# design1.net
KiCad netlist of a schematic drawn in EAGLE
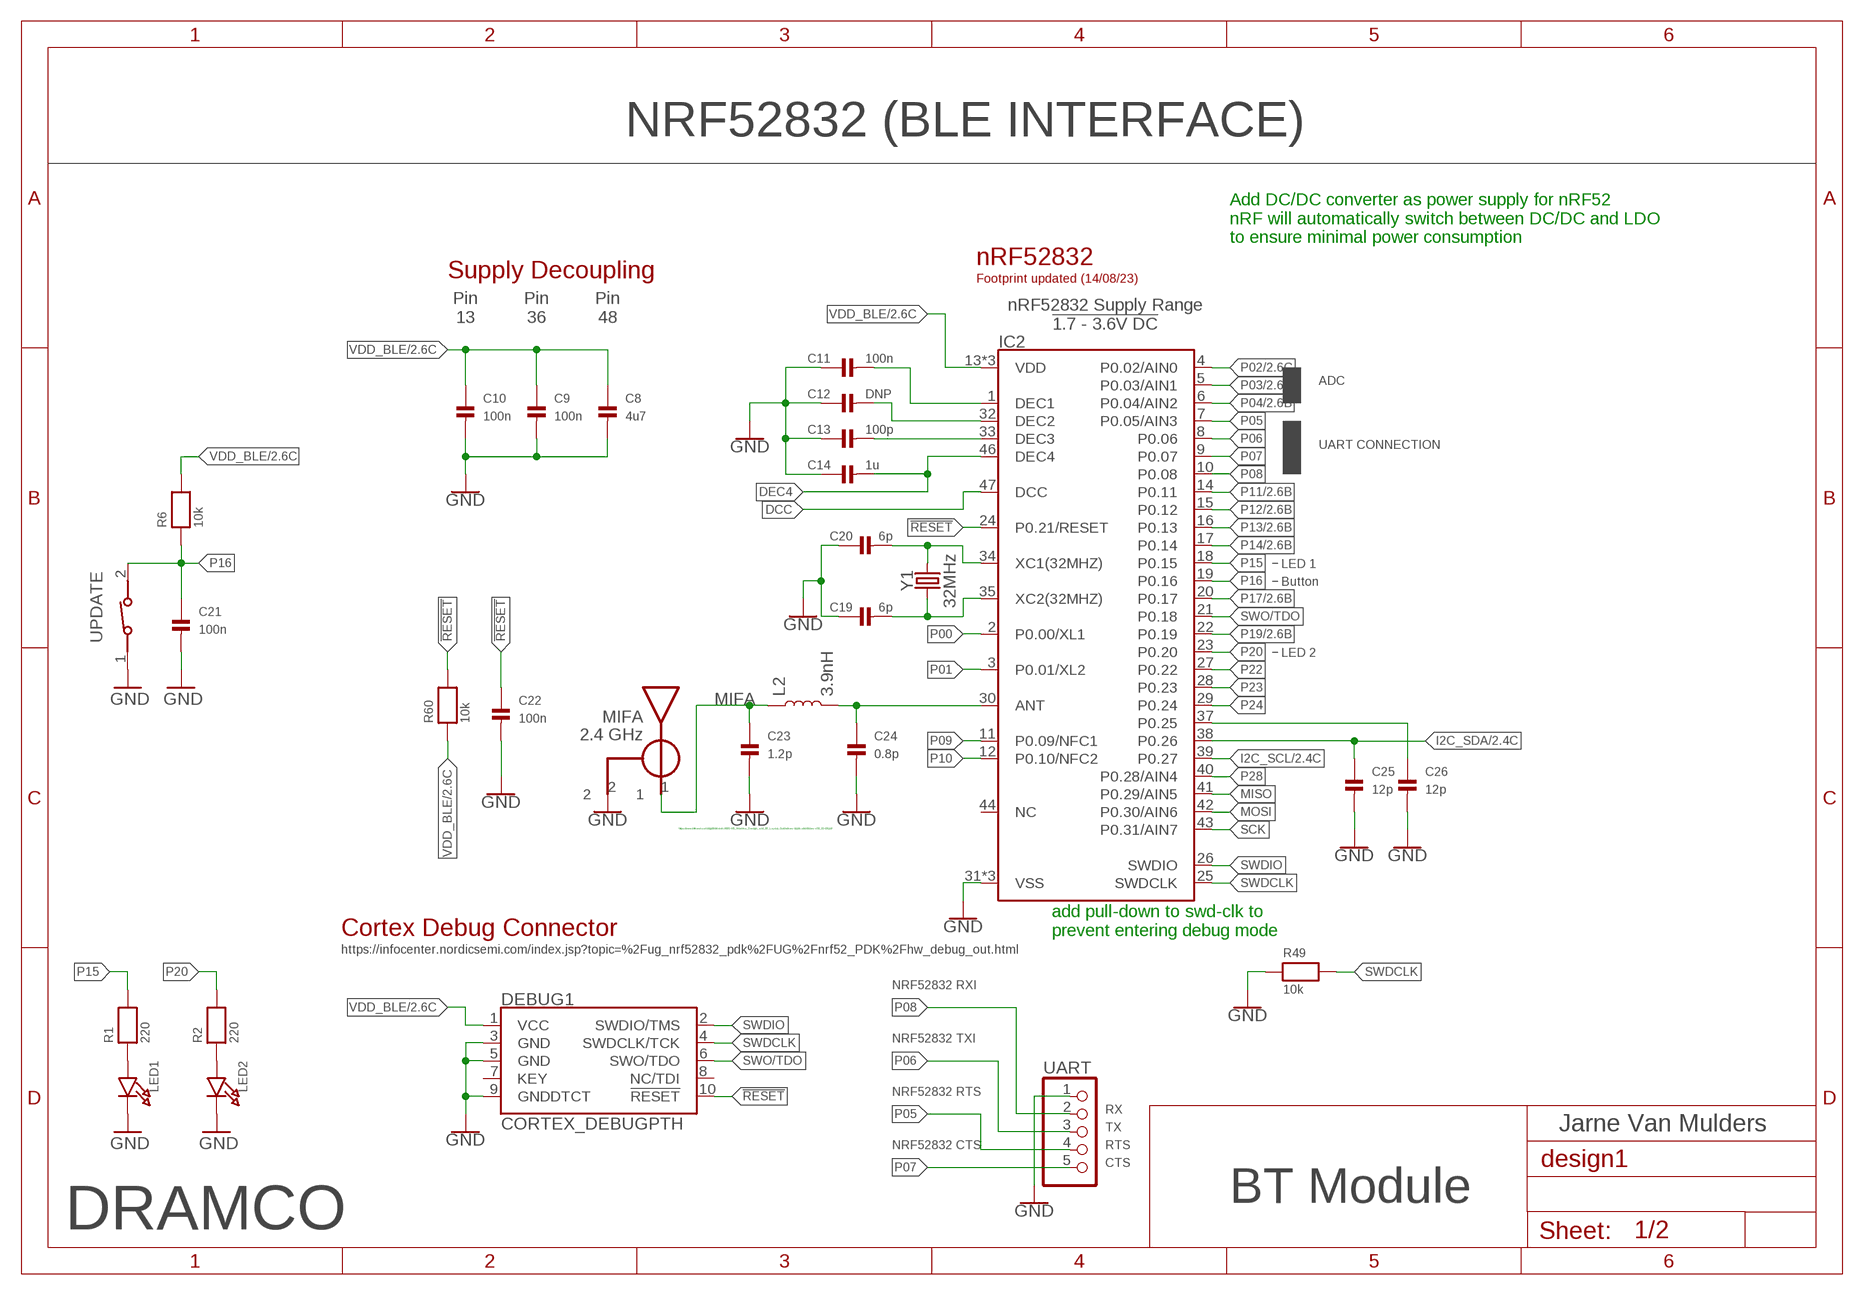
[diagram p0: schematic, sheet 1]
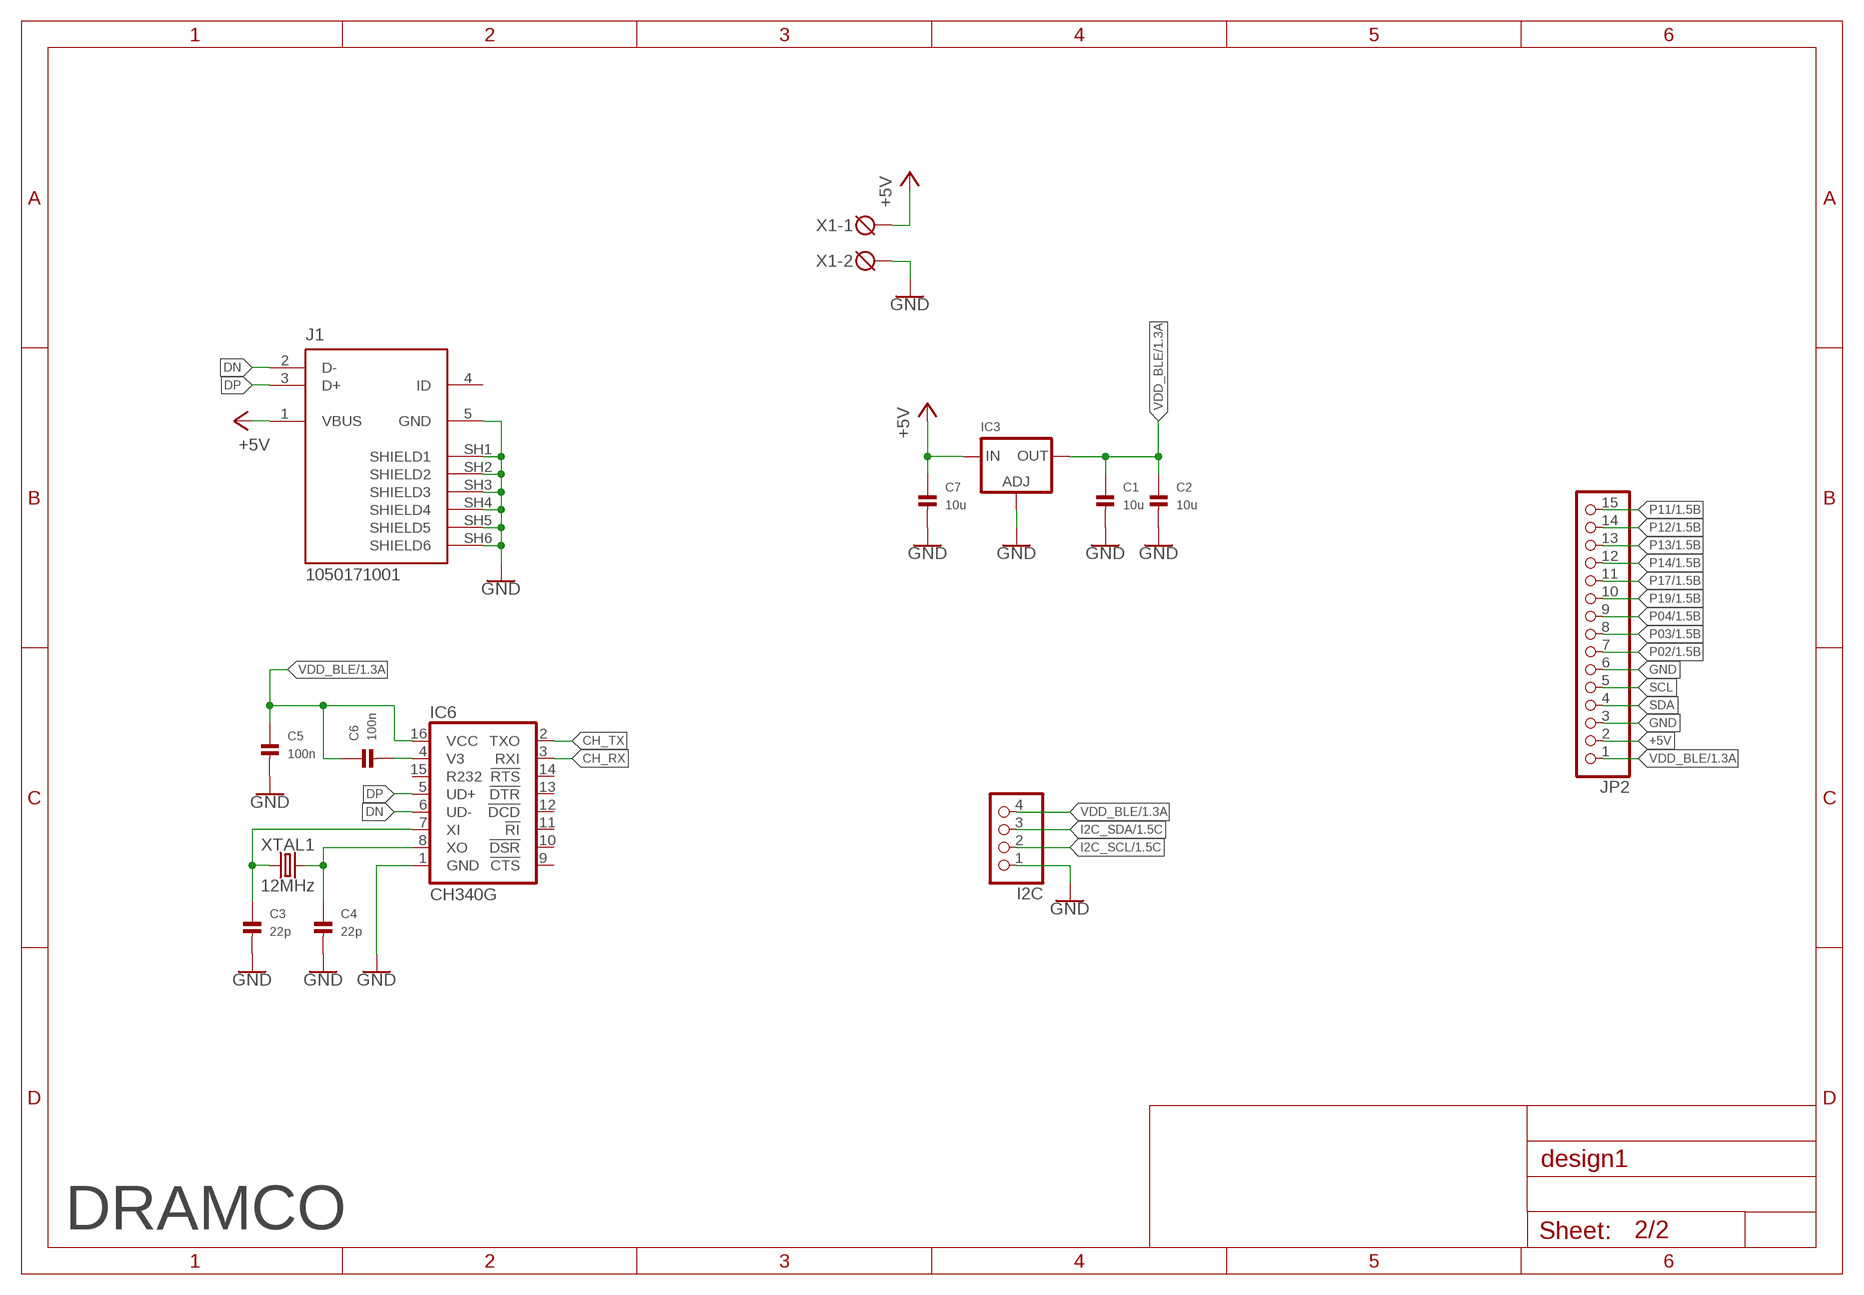
[diagram p1: schematic, sheet 2]

(export (version "E")
  (design (tool "Eeschema 10.0.6"))
  (components
    (comp (ref "C1")
      (value "10u")
      (footprint "eagle-import:0805")
      (libsource (lib "eagle-import") (part "CAP_CERAMIC0805"))
    )
    (comp (ref "C2")
      (value "10u")
      (footprint "eagle-import:0805")
      (libsource (lib "eagle-import") (part "CAP_CERAMIC0805"))
    )
    (comp (ref "C3")
      (value "22p")
      (footprint "eagle-import:0402")
      (libsource (lib "eagle-import") (part "CAP_CERAMIC0402"))
    )
    (comp (ref "C4")
      (value "22p")
      (footprint "eagle-import:0402")
      (libsource (lib "eagle-import") (part "CAP_CERAMIC0402"))
    )
    (comp (ref "C5")
      (value "100n")
      (footprint "eagle-import:0402")
      (libsource (lib "eagle-import") (part "CAP_CERAMIC0402"))
    )
    (comp (ref "C6")
      (value "100n")
      (footprint "eagle-import:0402")
      (libsource (lib "eagle-import") (part "CAP_CERAMIC0402"))
    )
    (comp (ref "C7")
      (value "10u")
      (footprint "eagle-import:0805")
      (libsource (lib "eagle-import") (part "CAP_CERAMIC0805"))
    )
    (comp (ref "I2C")
      (value "HEADER-1X4ROUND")
      (footprint "eagle-import:1X04_ROUND")
      (libsource (lib "eagle-import") (part "HEADER-1X4ROUND"))
    )
    (comp (ref "IC3")
      (value "LM1117SOT223-REFLOW")
      (footprint "eagle-import:SOT223-R")
      (libsource (lib "eagle-import") (part "LM1117SOT223-REFLOW"))
    )
    (comp (ref "IC6")
      (value "CH340G")
      (footprint "eagle-import:SO016")
      (libsource (lib "eagle-import") (part "CH340GSMD"))
    )
    (comp (ref "J1")
      (value "1050171001")
      (footprint "eagle-import:MOLEX_1050171001")
      (fields (field (name "MF") "Molex"))
      (libsource (lib "eagle-import") (part "1050171001"))
    )
    (comp (ref "JP2")
      (value "HEADER-1X15")
      (footprint "eagle-import:1X15_ROUND_70")
      (libsource (lib "eagle-import") (part "HEADER-1X15"))
    )
    (comp (ref "X1")
      (value "DG3XX-02-3.5")
      (footprint "eagle-import:DG350-3.5-02P")
      (libsource (lib "eagle-import") (part "DG3XX-02-3.5"))
    )
    (comp (ref "XTAL1")
      (value "12MHz")
      (footprint "eagle-import:CRYSTAL-SMD-3.2X2.5MM")
      (libsource (lib "eagle-import") (part "CRYSTALSMD-3.2X2.5"))
    )
    (comp (ref "C8")
      (value "4u7")
      (footprint "eagle-import:0603")
      (libsource (lib "eagle-import") (part "CAP_CERAMIC0603"))
    )
    (comp (ref "C9")
      (value "100n")
      (footprint "eagle-import:0402")
      (libsource (lib "eagle-import") (part "CAP_CERAMIC0402"))
    )
    (comp (ref "C10")
      (value "100n")
      (footprint "eagle-import:0402")
      (libsource (lib "eagle-import") (part "CAP_CERAMIC0402"))
    )
    (comp (ref "C11")
      (value "100n")
      (footprint "eagle-import:0402")
      (libsource (lib "eagle-import") (part "CAP_CERAMIC0402"))
    )
    (comp (ref "C12")
      (value "DNP")
      (footprint "eagle-import:0402")
      (libsource (lib "eagle-import") (part "CAP_CERAMIC0402"))
    )
    (comp (ref "C13")
      (value "100p")
      (footprint "eagle-import:0402")
      (libsource (lib "eagle-import") (part "CAP_CERAMIC0402"))
    )
    (comp (ref "C14")
      (value "1u")
      (footprint "eagle-import:0402")
      (libsource (lib "eagle-import") (part "CAP_CERAMIC0402"))
    )
    (comp (ref "C19")
      (value "6p")
      (footprint "eagle-import:0402")
      (libsource (lib "eagle-import") (part "CAP_CERAMIC0402"))
    )
    (comp (ref "C20")
      (value "6p")
      (footprint "eagle-import:0402")
      (libsource (lib "eagle-import") (part "CAP_CERAMIC0402"))
    )
    (comp (ref "C21")
      (value "100n")
      (footprint "eagle-import:0402")
      (libsource (lib "eagle-import") (part "CAP_CERAMIC0402"))
    )
    (comp (ref "C22")
      (value "100n")
      (footprint "eagle-import:0402")
      (libsource (lib "eagle-import") (part "CAP_CERAMIC0402"))
    )
    (comp (ref "C23")
      (value "1.2p")
      (footprint "eagle-import:0402")
      (libsource (lib "eagle-import") (part "CAP_CERAMIC0402"))
    )
    (comp (ref "C24")
      (value "0.8p")
      (footprint "eagle-import:0402")
      (libsource (lib "eagle-import") (part "CAP_CERAMIC0402"))
    )
    (comp (ref "C25")
      (value "12p")
      (footprint "eagle-import:0402")
      (libsource (lib "eagle-import") (part "CAP_CERAMIC0402"))
    )
    (comp (ref "C26")
      (value "12p")
      (footprint "eagle-import:0402")
      (libsource (lib "eagle-import") (part "CAP_CERAMIC0402"))
    )
    (comp (ref "DEBUG1")
      (value "CORTEX_DEBUGPTH")
      (footprint "eagle-import:2X5-PTH-1.27MM")
      (libsource (lib "eagle-import") (part "CORTEX_DEBUGPTH"))
    )
    (comp (ref "IC2")
      (value "NRF52832-EXTENDED")
      (footprint "eagle-import:QFN48-6X6MM-EXTENDED")
      (libsource (lib "eagle-import") (part "NRF52832-EXTENDED"))
    )
    (comp (ref "L2")
      (value "3.9nH")
      (footprint "eagle-import:0402")
      (libsource (lib "eagle-import") (part "INDUCTOR-0402-3.9NH"))
    )
    (comp (ref "LED1")
      (value "LED0805")
      (footprint "eagle-import:CHIPLED_0805")
      (libsource (lib "eagle-import") (part "LED0805"))
    )
    (comp (ref "LED2")
      (value "LED0805")
      (footprint "eagle-import:CHIPLED_0805")
      (libsource (lib "eagle-import") (part "LED0805"))
    )
    (comp (ref "R1")
      (value "220")
      (footprint "eagle-import:0603")
      (libsource (lib "eagle-import") (part "RESISTOR0603"))
    )
    (comp (ref "R2")
      (value "220")
      (footprint "eagle-import:0603")
      (libsource (lib "eagle-import") (part "RESISTOR0603"))
    )
    (comp (ref "R6")
      (value "10k")
      (footprint "eagle-import:0402")
      (libsource (lib "eagle-import") (part "RESISTOR0402"))
    )
    (comp (ref "R49")
      (value "10k")
      (footprint "eagle-import:0402")
      (libsource (lib "eagle-import") (part "RESISTOR0402"))
    )
    (comp (ref "R60")
      (value "10k")
      (footprint "eagle-import:0402")
      (libsource (lib "eagle-import") (part "RESISTOR0402"))
    )
    (comp (ref "U$18")
      (value "BLE-ANT")
      (footprint "eagle-import:ANT-2G4")
      (libsource (lib "eagle-import") (part "BLE-ANT"))
    )
    (comp (ref "UART")
      (value "HEADER-1X5ROUND")
      (footprint "eagle-import:1X05_ROUND")
      (libsource (lib "eagle-import") (part "HEADER-1X5ROUND"))
    )
    (comp (ref "UPDATE")
      (value "434111043826")
      (footprint "eagle-import:434111043826")
      (libsource (lib "eagle-import") (part "434111043826"))
    )
    (comp (ref "Y1")
      (value "32MHz")
      (footprint "eagle-import:CRYSTAL-SMD-2.0X1.6MM")
      (libsource (lib "eagle-import") (part "CRYSTAL-32MHZ-SMD-2.0X1.6MM"))
    )
  )
  (nets
    (net (code "1") (name "+5V") (class "Default")
      (node (ref "C7") (pin "1") (pinfunction "P$1_1") (pintype "passive"))
      (node (ref "IC3") (pin "3") (pinfunction "IN_3") (pintype "input"))
      (node (ref "J1") (pin "1") (pinfunction "VBUS_1") (pintype "power_in"))
      (node (ref "JP2") (pin "2") (pinfunction "2_2") (pintype "passive"))
      (node (ref "X1") (pin "1") (pinfunction "KL_1") (pintype "passive"))
    )
    (net (code "2") (name "CH_RX") (class "Default")
      (node (ref "IC6") (pin "3") (pinfunction "RXI_3") (pintype "bidirectional"))
    )
    (net (code "3") (name "CH_TX") (class "Default")
      (node (ref "IC6") (pin "2") (pinfunction "TXO_2") (pintype "bidirectional"))
    )
    (net (code "4") (name "DCC") (class "Default")
      (node (ref "IC2") (pin "47") (pinfunction "DCC_47") (pintype "bidirectional"))
    )
    (net (code "5") (name "DEC4") (class "Default")
      (node (ref "C14") (pin "2") (pinfunction "P$2_2") (pintype "passive"))
      (node (ref "IC2") (pin "46") (pinfunction "DEC4_46") (pintype "bidirectional"))
    )
    (net (code "6") (name "DN") (class "Default")
      (node (ref "IC6") (pin "6") (pinfunction "UD-_6") (pintype "bidirectional"))
      (node (ref "J1") (pin "2") (pinfunction "D-_2") (pintype "bidirectional"))
    )
    (net (code "7") (name "DP") (class "Default")
      (node (ref "IC6") (pin "5") (pinfunction "UD+_5") (pintype "bidirectional"))
      (node (ref "J1") (pin "3") (pinfunction "D+_3") (pintype "bidirectional"))
    )
    (net (code "8") (name "GND") (class "Default")
      (node (ref "C1") (pin "2") (pinfunction "P$2_2") (pintype "passive"))
      (node (ref "C10") (pin "2") (pinfunction "P$2_2") (pintype "passive"))
      (node (ref "C11") (pin "1") (pinfunction "P$1_1") (pintype "passive"))
      (node (ref "C12") (pin "1") (pinfunction "P$1_1") (pintype "passive"))
      (node (ref "C13") (pin "1") (pinfunction "P$1_1") (pintype "passive"))
      (node (ref "C14") (pin "1") (pinfunction "P$1_1") (pintype "passive"))
      (node (ref "C19") (pin "1") (pinfunction "P$1_1") (pintype "passive"))
      (node (ref "C2") (pin "2") (pinfunction "P$2_2") (pintype "passive"))
      (node (ref "C20") (pin "1") (pinfunction "P$1_1") (pintype "passive"))
      (node (ref "C21") (pin "2") (pinfunction "P$2_2") (pintype "passive"))
      (node (ref "C22") (pin "2") (pinfunction "P$2_2") (pintype "passive"))
      (node (ref "C23") (pin "2") (pinfunction "P$2_2") (pintype "passive"))
      (node (ref "C24") (pin "2") (pinfunction "P$2_2") (pintype "passive"))
      (node (ref "C25") (pin "2") (pinfunction "P$2_2") (pintype "passive"))
      (node (ref "C26") (pin "2") (pinfunction "P$2_2") (pintype "passive"))
      (node (ref "C3") (pin "2") (pinfunction "P$2_2") (pintype "passive"))
      (node (ref "C4") (pin "2") (pinfunction "P$2_2") (pintype "passive"))
      (node (ref "C5") (pin "2") (pinfunction "P$2_2") (pintype "passive"))
      (node (ref "C7") (pin "2") (pinfunction "P$2_2") (pintype "passive"))
      (node (ref "C8") (pin "2") (pinfunction "P$2_2") (pintype "passive"))
      (node (ref "C9") (pin "2") (pinfunction "P$2_2") (pintype "passive"))
      (node (ref "DEBUG1") (pin "3") (pinfunction "GND_3") (pintype "bidirectional"))
      (node (ref "DEBUG1") (pin "5") (pinfunction "GND_5") (pintype "bidirectional"))
      (node (ref "DEBUG1") (pin "9") (pinfunction "GNDDTCT_9") (pintype "bidirectional"))
      (node (ref "I2C") (pin "1") (pinfunction "1_1") (pintype "passive"))
      (node (ref "IC2") (pin "31") (pinfunction "VSS_31") (pintype "bidirectional"))
      (node (ref "IC2") (pin "45") (pinfunction "VSS_45") (pintype "bidirectional"))
      (node (ref "IC2") (pin "EP") (pinfunction "VSS_EP") (pintype "bidirectional"))
      (node (ref "IC3") (pin "1") (pinfunction "ADJ_1") (pintype "input"))
      (node (ref "IC6") (pin "1") (pinfunction "GND_1") (pintype "bidirectional"))
      (node (ref "J1") (pin "5") (pinfunction "GND_5") (pintype "power_in"))
      (node (ref "J1") (pin "SH1") (pinfunction "SHIELD1_SH1") (pintype "passive"))
      (node (ref "J1") (pin "SH2") (pinfunction "SHIELD2_SH2") (pintype "passive"))
      (node (ref "J1") (pin "SH3") (pinfunction "SHIELD3_SH3") (pintype "passive"))
      (node (ref "J1") (pin "SH4") (pinfunction "SHIELD4_SH4") (pintype "passive"))
      (node (ref "J1") (pin "SH5") (pinfunction "SHIELD5_SH5") (pintype "passive"))
      (node (ref "J1") (pin "SH6") (pinfunction "SHIELD6_SH6") (pintype "passive"))
      (node (ref "JP2") (pin "3") (pinfunction "3_3") (pintype "passive"))
      (node (ref "JP2") (pin "6") (pinfunction "6_6") (pintype "passive"))
      (node (ref "LED1") (pin "C") (pinfunction "C_C") (pintype "passive"))
      (node (ref "LED2") (pin "C") (pinfunction "C_C") (pintype "passive"))
      (node (ref "R49") (pin "1") (pinfunction "1_1") (pintype "passive"))
      (node (ref "U$18") (pin "2") (pinfunction "2_2") (pintype "bidirectional"))
      (node (ref "UART") (pin "1") (pinfunction "1_1") (pintype "passive"))
      (node (ref "UPDATE") (pin "1") (pinfunction "1_1") (pintype "passive"))
      (node (ref "X1") (pin "2") (pinfunction "KL_2") (pintype "passive"))
    )
    (net (code "9") (name "I2C_SCL") (class "Default")
      (node (ref "I2C") (pin "2") (pinfunction "2_2") (pintype "passive"))
      (node (ref "IC2") (pin "39") (pinfunction "P0.27_39") (pintype "bidirectional"))
    )
    (net (code "10") (name "I2C_SDA") (class "Default")
      (node (ref "C25") (pin "1") (pinfunction "P$1_1") (pintype "passive"))
      (node (ref "I2C") (pin "3") (pinfunction "3_3") (pintype "passive"))
      (node (ref "IC2") (pin "38") (pinfunction "P0.26_38") (pintype "bidirectional"))
    )
    (net (code "11") (name "MIFA") (class "Default")
      (node (ref "C23") (pin "1") (pinfunction "P$1_1") (pintype "passive"))
      (node (ref "L2") (pin "1") (pinfunction "1_1") (pintype "passive"))
      (node (ref "U$18") (pin "1") (pinfunction "1_1") (pintype "bidirectional"))
    )
    (net (code "12") (name "MISO") (class "Default")
      (node (ref "IC2") (pin "41") (pinfunction "P0.29/AIN5_41") (pintype "bidirectional"))
    )
    (net (code "13") (name "MOSI") (class "Default")
      (node (ref "IC2") (pin "42") (pinfunction "P0.30/AIN6_42") (pintype "bidirectional"))
    )
    (net (code "14") (name "Net-(C3-P$1)") (class "Default")
      (node (ref "C3") (pin "1") (pinfunction "P$1_1") (pintype "passive"))
      (node (ref "IC6") (pin "7") (pinfunction "XI_7") (pintype "bidirectional"))
      (node (ref "XTAL1") (pin "1") (pinfunction "1_1") (pintype "passive"))
    )
    (net (code "15") (name "Net-(C4-P$1)") (class "Default")
      (node (ref "C4") (pin "1") (pinfunction "P$1_1") (pintype "passive"))
      (node (ref "IC6") (pin "8") (pinfunction "XO_8") (pintype "bidirectional"))
      (node (ref "XTAL1") (pin "3") (pinfunction "2_3") (pintype "passive"))
    )
    (net (code "16") (name "Net-(C6-P$2)") (class "Default")
      (node (ref "C6") (pin "2") (pinfunction "P$2_2") (pintype "passive"))
      (node (ref "IC6") (pin "4") (pinfunction "V3_4") (pintype "bidirectional"))
    )
    (net (code "17") (name "Net-(C11-P$2)") (class "Default")
      (node (ref "C11") (pin "2") (pinfunction "P$2_2") (pintype "passive"))
      (node (ref "IC2") (pin "1") (pinfunction "DEC1_1") (pintype "bidirectional"))
    )
    (net (code "18") (name "Net-(C12-P$2)") (class "Default")
      (node (ref "C12") (pin "2") (pinfunction "P$2_2") (pintype "passive"))
      (node (ref "IC2") (pin "32") (pinfunction "DEC2_32") (pintype "bidirectional"))
    )
    (net (code "19") (name "Net-(C13-P$2)") (class "Default")
      (node (ref "C13") (pin "2") (pinfunction "P$2_2") (pintype "passive"))
      (node (ref "IC2") (pin "33") (pinfunction "DEC3_33") (pintype "bidirectional"))
    )
    (net (code "20") (name "Net-(C19-P$2)") (class "Default")
      (node (ref "C19") (pin "2") (pinfunction "P$2_2") (pintype "passive"))
      (node (ref "IC2") (pin "35") (pinfunction "XC2(32MHZ)_35") (pintype "bidirectional"))
      (node (ref "Y1") (pin "1") (pinfunction "1_1") (pintype "passive"))
    )
    (net (code "21") (name "Net-(C20-P$2)") (class "Default")
      (node (ref "C20") (pin "2") (pinfunction "P$2_2") (pintype "passive"))
      (node (ref "IC2") (pin "34") (pinfunction "XC1(32MHZ)_34") (pintype "bidirectional"))
      (node (ref "Y1") (pin "3") (pinfunction "2_3") (pintype "passive"))
    )
    (net (code "22") (name "Net-(C24-P$1)") (class "Default")
      (node (ref "C24") (pin "1") (pinfunction "P$1_1") (pintype "passive"))
      (node (ref "IC2") (pin "30") (pinfunction "ANT_30") (pintype "bidirectional"))
      (node (ref "L2") (pin "2") (pinfunction "2_2") (pintype "passive"))
    )
    (net (code "23") (name "Net-(C26-P$1)") (class "Default")
      (node (ref "C26") (pin "1") (pinfunction "P$1_1") (pintype "passive"))
      (node (ref "IC2") (pin "37") (pinfunction "P0.25_37") (pintype "bidirectional"))
    )
    (net (code "24") (name "Net-(LED1-PadA)") (class "Default")
      (node (ref "LED1") (pin "A") (pinfunction "A_A") (pintype "passive"))
      (node (ref "R1") (pin "1") (pinfunction "1_1") (pintype "passive"))
    )
    (net (code "25") (name "Net-(LED2-PadA)") (class "Default")
      (node (ref "LED2") (pin "A") (pinfunction "A_A") (pintype "passive"))
      (node (ref "R2") (pin "1") (pinfunction "1_1") (pintype "passive"))
    )
    (net (code "26") (name "P00") (class "Default")
      (node (ref "IC2") (pin "2") (pinfunction "P0.00/XL1_2") (pintype "bidirectional"))
    )
    (net (code "27") (name "P01") (class "Default")
      (node (ref "IC2") (pin "3") (pinfunction "P0.01/XL2_3") (pintype "bidirectional"))
    )
    (net (code "28") (name "P02") (class "Default")
      (node (ref "IC2") (pin "4") (pinfunction "P0.02/AIN0_4") (pintype "bidirectional"))
      (node (ref "JP2") (pin "7") (pinfunction "7_7") (pintype "passive"))
    )
    (net (code "29") (name "P03") (class "Default")
      (node (ref "IC2") (pin "5") (pinfunction "P0.03/AIN1_5") (pintype "bidirectional"))
      (node (ref "JP2") (pin "8") (pinfunction "8_8") (pintype "passive"))
    )
    (net (code "30") (name "P04") (class "Default")
      (node (ref "IC2") (pin "6") (pinfunction "P0.04/AIN2_6") (pintype "bidirectional"))
      (node (ref "JP2") (pin "9") (pinfunction "9_9") (pintype "passive"))
    )
    (net (code "31") (name "P05") (class "Default")
      (node (ref "IC2") (pin "7") (pinfunction "P0.05/AIN3_7") (pintype "bidirectional"))
      (node (ref "UART") (pin "4") (pinfunction "4_4") (pintype "passive"))
    )
    (net (code "32") (name "P06") (class "Default")
      (node (ref "IC2") (pin "8") (pinfunction "P0.06_8") (pintype "bidirectional"))
      (node (ref "UART") (pin "3") (pinfunction "3_3") (pintype "passive"))
    )
    (net (code "33") (name "P07") (class "Default")
      (node (ref "IC2") (pin "9") (pinfunction "P0.07_9") (pintype "bidirectional"))
      (node (ref "UART") (pin "5") (pinfunction "5_5") (pintype "passive"))
    )
    (net (code "34") (name "P08") (class "Default")
      (node (ref "IC2") (pin "10") (pinfunction "P0.08_10") (pintype "bidirectional"))
      (node (ref "UART") (pin "2") (pinfunction "2_2") (pintype "passive"))
    )
    (net (code "35") (name "P09") (class "Default")
      (node (ref "IC2") (pin "11") (pinfunction "P0.09/NFC1_11") (pintype "bidirectional"))
    )
    (net (code "36") (name "P10") (class "Default")
      (node (ref "IC2") (pin "12") (pinfunction "P0.10/NFC2_12") (pintype "bidirectional"))
    )
    (net (code "37") (name "P11") (class "Default")
      (node (ref "IC2") (pin "14") (pinfunction "P0.11_14") (pintype "bidirectional"))
      (node (ref "JP2") (pin "15") (pinfunction "15_15") (pintype "passive"))
    )
    (net (code "38") (name "P12") (class "Default")
      (node (ref "IC2") (pin "15") (pinfunction "P0.12_15") (pintype "bidirectional"))
      (node (ref "JP2") (pin "14") (pinfunction "14_14") (pintype "passive"))
    )
    (net (code "39") (name "P13") (class "Default")
      (node (ref "IC2") (pin "16") (pinfunction "P0.13_16") (pintype "bidirectional"))
      (node (ref "JP2") (pin "13") (pinfunction "13_13") (pintype "passive"))
    )
    (net (code "40") (name "P14") (class "Default")
      (node (ref "IC2") (pin "17") (pinfunction "P0.14_17") (pintype "bidirectional"))
      (node (ref "JP2") (pin "12") (pinfunction "12_12") (pintype "passive"))
    )
    (net (code "41") (name "P15") (class "Default")
      (node (ref "IC2") (pin "18") (pinfunction "P0.15_18") (pintype "bidirectional"))
      (node (ref "R1") (pin "2") (pinfunction "2_2") (pintype "passive"))
    )
    (net (code "42") (name "P16") (class "Default")
      (node (ref "C21") (pin "1") (pinfunction "P$1_1") (pintype "passive"))
      (node (ref "IC2") (pin "19") (pinfunction "P0.16_19") (pintype "bidirectional"))
      (node (ref "R6") (pin "1") (pinfunction "1_1") (pintype "passive"))
      (node (ref "UPDATE") (pin "2") (pinfunction "2_2") (pintype "passive"))
    )
    (net (code "43") (name "P17") (class "Default")
      (node (ref "IC2") (pin "20") (pinfunction "P0.17_20") (pintype "bidirectional"))
      (node (ref "JP2") (pin "11") (pinfunction "11_11") (pintype "passive"))
    )
    (net (code "44") (name "P19") (class "Default")
      (node (ref "IC2") (pin "22") (pinfunction "P0.19_22") (pintype "bidirectional"))
      (node (ref "JP2") (pin "10") (pinfunction "10_10") (pintype "passive"))
    )
    (net (code "45") (name "P20") (class "Default")
      (node (ref "IC2") (pin "23") (pinfunction "P0.20_23") (pintype "bidirectional"))
      (node (ref "R2") (pin "2") (pinfunction "2_2") (pintype "passive"))
    )
    (net (code "46") (name "P22") (class "Default")
      (node (ref "IC2") (pin "27") (pinfunction "P0.22_27") (pintype "bidirectional"))
    )
    (net (code "47") (name "P23") (class "Default")
      (node (ref "IC2") (pin "28") (pinfunction "P0.23_28") (pintype "bidirectional"))
    )
    (net (code "48") (name "P24") (class "Default")
      (node (ref "IC2") (pin "29") (pinfunction "P0.24_29") (pintype "bidirectional"))
    )
    (net (code "49") (name "P28") (class "Default")
      (node (ref "IC2") (pin "40") (pinfunction "P0.28/AIN4_40") (pintype "bidirectional"))
    )
    (net (code "50") (name "SCK") (class "Default")
      (node (ref "IC2") (pin "43") (pinfunction "P0.31/AIN7_43") (pintype "bidirectional"))
    )
    (net (code "51") (name "SCL") (class "Default")
      (node (ref "JP2") (pin "5") (pinfunction "5_5") (pintype "passive"))
    )
    (net (code "52") (name "SDA") (class "Default")
      (node (ref "JP2") (pin "4") (pinfunction "4_4") (pintype "passive"))
    )
    (net (code "53") (name "SWDCLK") (class "Default")
      (node (ref "DEBUG1") (pin "4") (pinfunction "SWDCLK/TCK_4") (pintype "bidirectional"))
      (node (ref "IC2") (pin "25") (pinfunction "SWDCLK_25") (pintype "bidirectional"))
      (node (ref "R49") (pin "2") (pinfunction "2_2") (pintype "passive"))
    )
    (net (code "54") (name "SWDIO") (class "Default")
      (node (ref "DEBUG1") (pin "2") (pinfunction "SWDIO/TMS_2") (pintype "bidirectional"))
      (node (ref "IC2") (pin "26") (pinfunction "SWDIO_26") (pintype "bidirectional"))
    )
    (net (code "55") (name "SWO{slash}TDO") (class "Default")
      (node (ref "DEBUG1") (pin "6") (pinfunction "SWO/TDO_6") (pintype "bidirectional"))
      (node (ref "IC2") (pin "21") (pinfunction "P0.18_21") (pintype "bidirectional"))
    )
    (net (code "56") (name "VDD_BLE") (class "Default")
      (node (ref "C1") (pin "1") (pinfunction "P$1_1") (pintype "passive"))
      (node (ref "C10") (pin "1") (pinfunction "P$1_1") (pintype "passive"))
      (node (ref "C2") (pin "1") (pinfunction "P$1_1") (pintype "passive"))
      (node (ref "C5") (pin "1") (pinfunction "P$1_1") (pintype "passive"))
      (node (ref "C6") (pin "1") (pinfunction "P$1_1") (pintype "passive"))
      (node (ref "C8") (pin "1") (pinfunction "P$1_1") (pintype "passive"))
      (node (ref "C9") (pin "1") (pinfunction "P$1_1") (pintype "passive"))
      (node (ref "DEBUG1") (pin "1") (pinfunction "VCC_1") (pintype "bidirectional"))
      (node (ref "I2C") (pin "4") (pinfunction "4_4") (pintype "passive"))
      (node (ref "IC2") (pin "13") (pinfunction "VDD_13") (pintype "bidirectional"))
      (node (ref "IC2") (pin "36") (pinfunction "VDD_36") (pintype "bidirectional"))
      (node (ref "IC2") (pin "48") (pinfunction "VDD_48") (pintype "bidirectional"))
      (node (ref "IC3") (pin "2") (pinfunction "OUT_2") (pintype "passive"))
      (node (ref "IC6") (pin "16") (pinfunction "VCC_16") (pintype "bidirectional"))
      (node (ref "JP2") (pin "1") (pinfunction "1_1") (pintype "passive"))
      (node (ref "R6") (pin "2") (pinfunction "2_2") (pintype "passive"))
      (node (ref "R60") (pin "1") (pinfunction "1_1") (pintype "passive"))
    )
    (net (code "57") (name "unconnected-(DEBUG1-KEY-Pad7)") (class "Default")
      (node (ref "DEBUG1") (pin "7") (pinfunction "KEY_7") (pintype "bidirectional"))
    )
    (net (code "58") (name "unconnected-(DEBUG1-NC{slash}TDI-Pad8)") (class "Default")
      (node (ref "DEBUG1") (pin "8") (pinfunction "NC/TDI_8") (pintype "bidirectional"))
    )
    (net (code "59") (name "unconnected-(IC2-NC-Pad44)") (class "Default")
      (node (ref "IC2") (pin "44") (pinfunction "NC_44") (pintype "bidirectional"))
    )
    (net (code "60") (name "unconnected-(IC6-R232-Pad15)") (class "Default")
      (node (ref "IC6") (pin "15") (pinfunction "R232_15") (pintype "bidirectional"))
    )
    (net (code "61") (name "unconnected-(IC6-~{CTS}-Pad9)") (class "Default")
      (node (ref "IC6") (pin "9") (pinfunction "~{CTS}_9") (pintype "bidirectional"))
    )
    (net (code "62") (name "unconnected-(IC6-~{DCD}-Pad12)") (class "Default")
      (node (ref "IC6") (pin "12") (pinfunction "~{DCD}_12") (pintype "bidirectional"))
    )
    (net (code "63") (name "unconnected-(IC6-~{DSR}-Pad10)") (class "Default")
      (node (ref "IC6") (pin "10") (pinfunction "~{DSR}_10") (pintype "bidirectional"))
    )
    (net (code "64") (name "unconnected-(IC6-~{DTR}-Pad13)") (class "Default")
      (node (ref "IC6") (pin "13") (pinfunction "~{DTR}_13") (pintype "bidirectional"))
    )
    (net (code "65") (name "unconnected-(IC6-~{RI}-Pad11)") (class "Default")
      (node (ref "IC6") (pin "11") (pinfunction "~{RI}_11") (pintype "bidirectional"))
    )
    (net (code "66") (name "unconnected-(IC6-~{RTS}-Pad14)") (class "Default")
      (node (ref "IC6") (pin "14") (pinfunction "~{RTS}_14") (pintype "bidirectional"))
    )
    (net (code "67") (name "unconnected-(J1-ID-Pad4)") (class "Default")
      (node (ref "J1") (pin "4") (pinfunction "ID_4") (pintype "bidirectional"))
    )
    (net (code "68") (name "~{RESET}") (class "Default")
      (node (ref "C22") (pin "1") (pinfunction "P$1_1") (pintype "passive"))
      (node (ref "DEBUG1") (pin "10") (pinfunction "~{RESET}_10") (pintype "bidirectional"))
      (node (ref "IC2") (pin "24") (pinfunction "P0.21/RESET_24") (pintype "bidirectional"))
      (node (ref "R60") (pin "2") (pinfunction "2_2") (pintype "passive"))
    )
  )
)
